# USB-OLED.net
KiCad netlist of a schematic drawn in Altium Designer
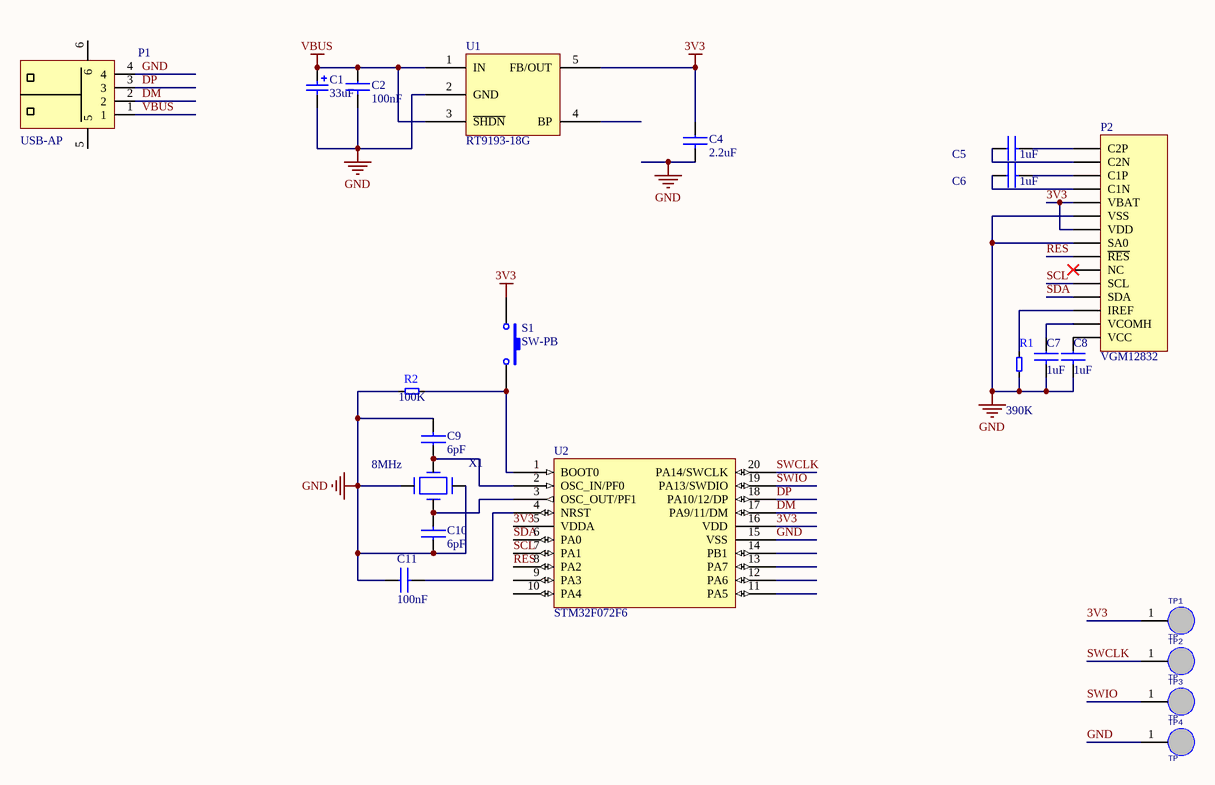
[diagram p0: USB-OLED.SchDoc]

(export (version "E")
  (design (tool "Eeschema 10.0.6"))
  (components
    (comp (ref "C1")
      (value "33uF")
      (footprint "C1206/A")
      (description "电容")
      (libsource (lib "tony") (part "CAP1206/A"))
    )
    (comp (ref "C2")
      (value "100nF")
      (footprint "C0603")
      (description "电容")
      (libsource (lib "tony") (part "CAP"))
    )
    (comp (ref "C4")
      (value "2.2uF")
      (footprint "C0603")
      (description "电容")
      (libsource (lib "tony") (part "CAP0805"))
    )
    (comp (ref "C5")
      (value "1uF")
      (footprint "C0603")
      (description "电容")
      (libsource (lib "tony") (part "CAP"))
    )
    (comp (ref "C6")
      (value "1uF")
      (footprint "C0603")
      (description "电容")
      (libsource (lib "tony") (part "CAP"))
    )
    (comp (ref "C7")
      (value "1uF")
      (footprint "C0603")
      (description "电容")
      (libsource (lib "tony") (part "CAP0805"))
    )
    (comp (ref "C8")
      (value "1uF")
      (footprint "C0603")
      (description "电容")
      (libsource (lib "tony") (part "CAP0805"))
    )
    (comp (ref "C9")
      (value "6pF")
      (footprint "C0603")
      (description "电容")
      (libsource (lib "tony") (part "CAP"))
    )
    (comp (ref "C10")
      (value "6pF")
      (footprint "C0603")
      (description "电容")
      (libsource (lib "tony") (part "CAP"))
    )
    (comp (ref "C11")
      (value "100nF")
      (footprint "C0603")
      (description "电容")
      (libsource (lib "tony") (part "CAP"))
    )
    (comp (ref "P1") (value "USB-AP") (footprint "USB-AP-SMT") (libsource (lib "tony") (part "USB-AP")))
    (comp (ref "P2") (value "VGM12832") (footprint "VGM12832B") (libsource (lib "tony") (part "VGM12832")))
    (comp (ref "R1")
      (value "390K")
      (footprint "R0603")
      (description "电阻")
      (libsource (lib "tony") (part "RES"))
    )
    (comp (ref "R2")
      (value "100K")
      (footprint "R0603")
      (description "电阻")
      (libsource (lib "tony") (part "RES"))
    )
    (comp (ref "S1")
      (value "SW-PB")
      (footprint "TS-1806B")
      (description "Switch")
      (fields (field (name "PUBLISHER") "Altium Limited"))
      (libsource (lib "Miscellaneous Devices") (part "SW-PB"))
    )
    (comp (ref "TP1")
      (value "TP")
      (footprint "TestPoint")
      (description "测试点")
      (libsource (lib "tony") (part "TP"))
    )
    (comp (ref "TP2")
      (value "TP")
      (footprint "TestPoint")
      (description "测试点")
      (libsource (lib "tony") (part "TP"))
    )
    (comp (ref "TP3")
      (value "TP")
      (footprint "TestPoint")
      (description "测试点")
      (libsource (lib "tony") (part "TP"))
    )
    (comp (ref "TP4")
      (value "TP")
      (footprint "TestPoint")
      (description "测试点")
      (libsource (lib "tony") (part "TP"))
    )
    (comp (ref "U1")
      (value "RT9193-18G")
      (footprint "SOT23-5")
      (description "芯片")
      (libsource (lib "tony") (part "RT9193"))
    )
    (comp (ref "U2")
      (value "STM32F072F6")
      (footprint "TSSOP20")
      (libsource (lib "tony") (part "STM32F072F6"))
    )
    (comp (ref "X1")
      (value "8MHz")
      (footprint "NX2520")
      (description "晶振")
      (libsource (lib "tony") (part "CRYSTAL4"))
    )
  )
  (nets
    (net (code "1") (name "/DM") (class "Default")
      (node (ref "P1") (pin "2") (pinfunction "2_2") (pintype "passive"))
      (node (ref "U2") (pin "17") (pinfunction "PA9/11/DM_17") (pintype "bidirectional"))
    )
    (net (code "2") (name "/DP") (class "Default")
      (node (ref "P1") (pin "3") (pinfunction "3_3") (pintype "passive"))
      (node (ref "U2") (pin "18") (pinfunction "PA10/12/DP_18") (pintype "bidirectional"))
    )
    (net (code "3") (name "/RES") (class "Default")
      (node (ref "P2") (pin "9") (pinfunction "~{RES}_9") (pintype "passive"))
      (node (ref "U2") (pin "8") (pinfunction "PA2_8") (pintype "bidirectional"))
    )
    (net (code "4") (name "/SCL") (class "Default")
      (node (ref "P2") (pin "11") (pinfunction "SCL_11") (pintype "passive"))
      (node (ref "U2") (pin "7") (pinfunction "PA1_7") (pintype "bidirectional"))
    )
    (net (code "5") (name "/SDA") (class "Default")
      (node (ref "P2") (pin "12") (pinfunction "SDA_12") (pintype "passive"))
      (node (ref "U2") (pin "6") (pinfunction "PA0_6") (pintype "bidirectional"))
    )
    (net (code "6") (name "/SWCLK") (class "Default")
      (node (ref "TP2") (pin "1") (pintype "passive"))
      (node (ref "U2") (pin "20") (pinfunction "PA14/SWCLK_20") (pintype "bidirectional"))
    )
    (net (code "7") (name "/SWIO") (class "Default")
      (node (ref "TP3") (pin "1") (pintype "passive"))
      (node (ref "U2") (pin "19") (pinfunction "PA13/SWDIO_19") (pintype "bidirectional"))
    )
    (net (code "8") (name "3V3") (class "Default")
      (node (ref "C4") (pin "1") (pinfunction "1_1") (pintype "passive"))
      (node (ref "P2") (pin "5") (pinfunction "VBAT_5") (pintype "passive"))
      (node (ref "P2") (pin "7") (pinfunction "VDD_7") (pintype "passive"))
      (node (ref "S1") (pin "1") (pinfunction "1_1") (pintype "passive"))
      (node (ref "TP1") (pin "1") (pintype "passive"))
      (node (ref "U1") (pin "5") (pinfunction "FB/OUT_5") (pintype "passive"))
      (node (ref "U2") (pin "16") (pinfunction "VDD_16") (pintype "power_in"))
      (node (ref "U2") (pin "5") (pinfunction "VDDA_5") (pintype "power_in"))
    )
    (net (code "9") (name "GND") (class "Default")
      (node (ref "C1") (pin "2") (pinfunction "2_2") (pintype "passive"))
      (node (ref "C10") (pin "1") (pinfunction "1_1") (pintype "passive"))
      (node (ref "C11") (pin "1") (pinfunction "1_1") (pintype "passive"))
      (node (ref "C2") (pin "2") (pinfunction "2_2") (pintype "passive"))
      (node (ref "C4") (pin "2") (pinfunction "2_2") (pintype "passive"))
      (node (ref "C7") (pin "2") (pinfunction "2_2") (pintype "passive"))
      (node (ref "C8") (pin "2") (pinfunction "2_2") (pintype "passive"))
      (node (ref "C9") (pin "2") (pinfunction "2_2") (pintype "passive"))
      (node (ref "P1") (pin "4") (pinfunction "4_4") (pintype "passive"))
      (node (ref "P2") (pin "6") (pinfunction "VSS_6") (pintype "passive"))
      (node (ref "P2") (pin "8") (pinfunction "SA0_8") (pintype "passive"))
      (node (ref "R1") (pin "1") (pintype "passive"))
      (node (ref "R2") (pin "2") (pintype "passive"))
      (node (ref "TP4") (pin "1") (pintype "passive"))
      (node (ref "U1") (pin "2") (pinfunction "GND_2") (pintype "passive"))
      (node (ref "U2") (pin "15") (pinfunction "VSS_15") (pintype "power_in"))
      (node (ref "X1") (pin "2") (pinfunction "2_2") (pintype "passive"))
      (node (ref "X1") (pin "4") (pinfunction "4_4") (pintype "passive"))
    )
    (net (code "10") (name "Net-(P2-C1N)") (class "Default")
      (node (ref "C6") (pin "1") (pinfunction "1_1") (pintype "passive"))
      (node (ref "P2") (pin "4") (pinfunction "C1N_4") (pintype "passive"))
    )
    (net (code "11") (name "Net-(P2-C1P)") (class "Default")
      (node (ref "C6") (pin "2") (pinfunction "2_2") (pintype "passive"))
      (node (ref "P2") (pin "3") (pinfunction "C1P_3") (pintype "passive"))
    )
    (net (code "12") (name "Net-(P2-C2N)") (class "Default")
      (node (ref "C5") (pin "1") (pinfunction "1_1") (pintype "passive"))
      (node (ref "P2") (pin "2") (pinfunction "C2N_2") (pintype "passive"))
    )
    (net (code "13") (name "Net-(P2-C2P)") (class "Default")
      (node (ref "C5") (pin "2") (pinfunction "2_2") (pintype "passive"))
      (node (ref "P2") (pin "1") (pinfunction "C2P_1") (pintype "passive"))
    )
    (net (code "14") (name "Net-(P2-IREF)") (class "Default")
      (node (ref "P2") (pin "13") (pinfunction "IREF_13") (pintype "passive"))
      (node (ref "R1") (pin "2") (pintype "passive"))
    )
    (net (code "15") (name "Net-(P2-VCC)") (class "Default")
      (node (ref "C8") (pin "1") (pinfunction "1_1") (pintype "passive"))
      (node (ref "P2") (pin "15") (pinfunction "VCC_15") (pintype "passive"))
    )
    (net (code "16") (name "Net-(P2-VCOMH)") (class "Default")
      (node (ref "C7") (pin "1") (pinfunction "1_1") (pintype "passive"))
      (node (ref "P2") (pin "14") (pinfunction "VCOMH_14") (pintype "passive"))
    )
    (net (code "17") (name "Net-(U2-BOOT0)") (class "Default")
      (node (ref "R2") (pin "1") (pintype "passive"))
      (node (ref "S1") (pin "2") (pinfunction "2_2") (pintype "passive"))
      (node (ref "U2") (pin "1") (pinfunction "BOOT0_1") (pintype "input"))
    )
    (net (code "18") (name "Net-(U2-NRST)") (class "Default")
      (node (ref "C11") (pin "2") (pinfunction "2_2") (pintype "passive"))
      (node (ref "U2") (pin "4") (pinfunction "NRST_4") (pintype "bidirectional"))
    )
    (net (code "19") (name "Net-(U2-OSC_IN{slash}PF0)") (class "Default")
      (node (ref "C9") (pin "1") (pinfunction "1_1") (pintype "passive"))
      (node (ref "U2") (pin "2") (pinfunction "OSC_IN/PF0_2") (pintype "input"))
      (node (ref "X1") (pin "3") (pinfunction "3_3") (pintype "passive"))
    )
    (net (code "20") (name "Net-(U2-OSC_OUT{slash}PF1)") (class "Default")
      (node (ref "C10") (pin "2") (pinfunction "2_2") (pintype "passive"))
      (node (ref "U2") (pin "3") (pinfunction "OSC_OUT/PF1_3") (pintype "output"))
      (node (ref "X1") (pin "1") (pinfunction "1_1") (pintype "passive"))
    )
    (net (code "21") (name "VBUS") (class "Default")
      (node (ref "C1") (pin "1") (pinfunction "1_1") (pintype "passive"))
      (node (ref "C2") (pin "1") (pinfunction "1_1") (pintype "passive"))
      (node (ref "P1") (pin "1") (pinfunction "1_1") (pintype "passive"))
      (node (ref "U1") (pin "1") (pinfunction "IN_1") (pintype "passive"))
      (node (ref "U1") (pin "3") (pinfunction "~{SHDN}_3") (pintype "passive"))
    )
    (net (code "22") (name "unconnected-(P1-Pad5)") (class "Default")
      (node (ref "P1") (pin "5") (pinfunction "5_5") (pintype "passive"))
    )
    (net (code "23") (name "unconnected-(P1-Pad6)") (class "Default")
      (node (ref "P1") (pin "6") (pinfunction "6_6") (pintype "passive"))
    )
    (net (code "24") (name "unconnected-(P2-NC-Pad10)") (class "Default")
      (node (ref "P2") (pin "10") (pinfunction "NC_10") (pintype "passive+no_connect"))
    )
    (net (code "25") (name "unconnected-(U1-BP-Pad4)") (class "Default")
      (node (ref "U1") (pin "4") (pinfunction "BP_4") (pintype "passive"))
    )
    (net (code "26") (name "unconnected-(U2-PA3-Pad9)") (class "Default")
      (node (ref "U2") (pin "9") (pinfunction "PA3_9") (pintype "bidirectional"))
    )
    (net (code "27") (name "unconnected-(U2-PA4-Pad10)") (class "Default")
      (node (ref "U2") (pin "10") (pinfunction "PA4_10") (pintype "bidirectional"))
    )
    (net (code "28") (name "unconnected-(U2-PA5-Pad11)") (class "Default")
      (node (ref "U2") (pin "11") (pinfunction "PA5_11") (pintype "bidirectional"))
    )
    (net (code "29") (name "unconnected-(U2-PA6-Pad12)") (class "Default")
      (node (ref "U2") (pin "12") (pinfunction "PA6_12") (pintype "bidirectional"))
    )
    (net (code "30") (name "unconnected-(U2-PA7-Pad13)") (class "Default")
      (node (ref "U2") (pin "13") (pinfunction "PA7_13") (pintype "bidirectional"))
    )
    (net (code "31") (name "unconnected-(U2-PB1-Pad14)") (class "Default")
      (node (ref "U2") (pin "14") (pinfunction "PB1_14") (pintype "bidirectional"))
    )
  )
)
